# Brakelight.net
KiCad netlist of a schematic drawn in Altium Designer
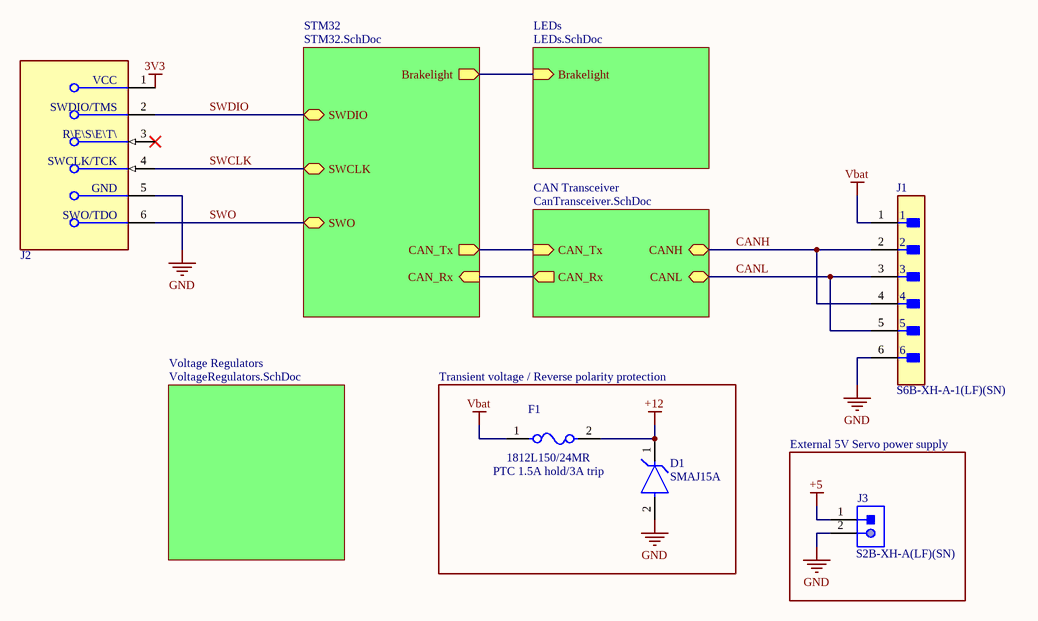
[diagram p0: Brakelight.SchDoc]

(export (version "E")
  (design (tool "Eeschema 10.0.6"))
  (components
    (comp (ref "D1")
      (value "SMAJ15A")
      (footprint "FP-SMA-MFG")
      (description "TVS DIODE 15V 24.4V SMA")
      (fields
        (field (name "OCTOPART") "https://octopart.com/smaj15a-bourns-12809353")
        (field (name "MANUFACTURER") "Bourns Inc.")
      )
      (libsource (lib "Altium Content Vault") (part "f813f71cba58e380607f5dd3caf9714"))
    )
    (comp (ref "F1")
      (value "1812L150/24MR")
      (footprint "FP-1812L-MFG")
      (description "PTC RESET FUSE 24V 1.5A 1812")
      (fields
        (field (name "MANUFACTURER") "Littelfuse Inc")
        (field (name "OCTOPART") "https://octopart.com/1812l150%2F24mr-littelfuse-7130198")
      )
      (libsource (lib "Altium Content Vault") (part "5bcf9b9f640e542cf0359d10258e979"))
    )
    (comp (ref "J1")
      (value "S6B-XH-A-1(LF)(SN)")
      (footprint "FP-S6B-XH-A-1_LF_SN-MFG")
      (description "CONN HEADER R/A P6OS 2.5MM")
      (libsource (lib "Altium Content Vault") (part "f2cb566baf1c37ab5a3b8e90bbeafd6"))
    )
    (comp (ref "J2")
      (value "TC2030-CTX-NL")
      (footprint "Tag_Connect_0_MFG")
      (libsource (lib "Conn_Tag_Connect_TC2030-CTX-NL_eec") (part "TC2030-CTX-NL"))
    )
    (comp (ref "J3")
      (value "S2B-XH-A(LF)(SN)")
      (footprint "JST-S2B-XH-A(LF)(SN)_V")
      (fields (field (name "TOLERANCE") "10%"))
      (libsource (lib "Altium Content Vault") (part "CN-1P-M-R2"))
    )
  )
  (nets
    (net (code "1") (name "+5") (class "Default")
      (node (ref "J3") (pin "1") (pinfunction "1_1") (pintype "passive"))
    )
    (net (code "2") (name "+12") (class "Default")
      (node (ref "D1") (pin "1") (pinfunction "C_1") (pintype "passive"))
      (node (ref "F1") (pin "2") (pinfunction "2_2") (pintype "passive"))
    )
    (net (code "4") (name "/CANH") (class "Default")
      (node (ref "J1") (pin "2") (pinfunction "2_2") (pintype "passive"))
      (node (ref "J1") (pin "4") (pinfunction "4_4") (pintype "passive"))
    )
    (net (code "5") (name "/CANL") (class "Default")
      (node (ref "J1") (pin "3") (pinfunction "3_3") (pintype "passive"))
      (node (ref "J1") (pin "5") (pinfunction "5_5") (pintype "passive"))
    )
    (net (code "8") (name "/SWCLK") (class "Default")
      (node (ref "J2") (pin "4") (pinfunction "SWCLK/TCK_4") (pintype "input"))
    )
    (net (code "9") (name "/SWDIO") (class "Default")
      (node (ref "J2") (pin "2") (pinfunction "SWDIO/TMS_2") (pintype "passive"))
    )
    (net (code "10") (name "/SWO") (class "Default")
      (node (ref "J2") (pin "6") (pinfunction "SWO/TDO_6") (pintype "passive"))
    )
    (net (code "11") (name "3V3") (class "Default")
      (node (ref "J2") (pin "1") (pinfunction "VCC_1") (pintype "power_in"))
    )
    (net (code "12") (name "GND") (class "Default")
      (node (ref "D1") (pin "2") (pinfunction "A_2") (pintype "passive"))
      (node (ref "J1") (pin "6") (pinfunction "6_6") (pintype "passive"))
      (node (ref "J2") (pin "5") (pinfunction "GND_5") (pintype "power_in"))
      (node (ref "J3") (pin "2") (pinfunction "2_2") (pintype "passive"))
    )
    (net (code "13") (name "Vbat") (class "Default")
      (node (ref "F1") (pin "1") (pinfunction "1_1") (pintype "passive"))
      (node (ref "J1") (pin "1") (pinfunction "1_1") (pintype "passive"))
    )
    (net (code "14") (name "unconnected-(J2-~{RESET}-Pad3)") (class "Default")
      (node (ref "J2") (pin "3") (pinfunction "~{RESET}_3") (pintype "input+no_connect"))
    )
  )
)
